# PLD_RTC.net
KiCad netlist of a schematic drawn in Altium Designer
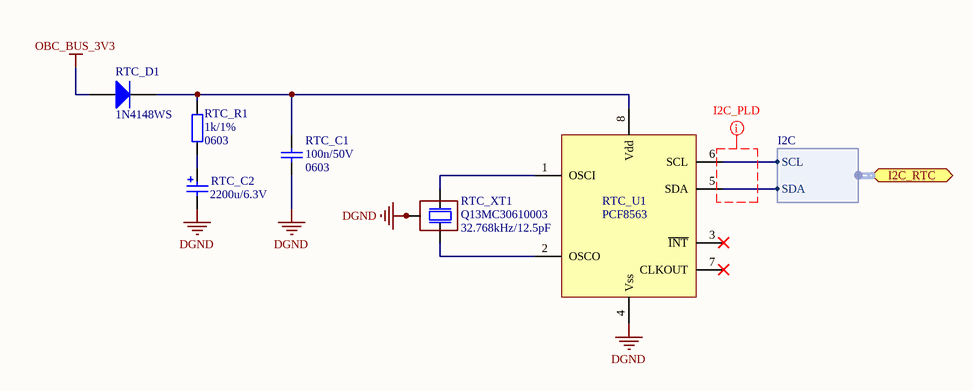
[diagram p0: PLD_RTC.SchDoc]

(export (version "E")
  (design (tool "Eeschema 10.0.6"))
  (components
    (comp (ref "RTC_C1")
      (value "100n/50V")
      (footprint "SMD_Capacitor_0603")
      (description "Ceramic Cap Kemet COTS 100n/50V X7R 0603")
      (fields
        (field (name "MANUFACTURER") "Kemet")
        (field (name "MANUFACTURERPARTNUMBER") "C0603T104K5RALTU")
        (field (name "PACKAGE") "0603")
      )
      (libsource (lib "capacitors") (part "Cer_C0603T104K5RALTU"))
    )
    (comp (ref "RTC_C2")
      (value "2200u/6.3V")
      (footprint "Tant_592D_X")
      (description "Vishay 592D Solid Tantalum Chip Capacitors.")
      (fields
        (field (name "MANUFACTURERPARTNUMBER") "592D228X96R3X2T20H")
        (field (name "MANUFACTURER") "Vishay")
      )
      (libsource (lib "capacitors") (part "Tant_592D228X96R3X2T20H"))
    )
    (comp (ref "RTC_D1")
      (value "1N4148WS")
      (footprint "SOD323")
      (description "Small Signal Fast Switching Diode")
      (fields (field (name "MANUFACTURER") "Vishay"))
      (libsource (lib "diodes") (part "1N4148WS"))
    )
    (comp (ref "RTC_R1")
      (value "1k/1%")
      (footprint "SMD_Resistor_0603")
      (description "1k/1% Vishay CRCW 0603 Resistor. 100mW, 100ppm, 75V.")
      (fields
        (field (name "MANUFACTURER") "Vishay")
        (field (name "MANUFACTURERPARTNUMBER") "CRCW06031K00FKxxxx")
        (field (name "PACKAGE") "0603")
      )
      (libsource (lib "resistors") (part "CRCW06031K00FKxxxx"))
    )
    (comp (ref "RTC_U1")
      (value "~")
      (footprint "TSSOP8_L")
      (description "Real-time clock/calendar")
      (fields (field (name "MANUFACTURER") "NXP") (field (name "MANUFACTURERPARTNUMBER") "PCF8563"))
      (libsource (lib "microcircuits") (part "PCF8563"))
    )
    (comp (ref "RTC_XT1")
      (value "32.768kHz/12.5pF")
      (footprint "Epson_MC-306")
      (description "EPSON MC-306 32.768KHZ 12.5pF Crystal")
      (fields (field (name "MANUFACTURER") "Epson") (field (name "MANUFACTURERPARTNUMBER") "Q13MC30610003"))
      (libsource (lib "crystal") (part "Q13MC30610003"))
    )
  )
  (nets
    (net (code "2") (name "/SCL") (class "Default")
      (node (ref "RTC_U1") (pin "6") (pinfunction "SCL_6") (pintype "passive"))
    )
    (net (code "3") (name "/SDA") (class "Default")
      (node (ref "RTC_U1") (pin "5") (pinfunction "SDA_5") (pintype "passive"))
    )
    (net (code "5") (name "DGND") (class "Default")
      (node (ref "RTC_C1") (pin "2") (pinfunction "2_2") (pintype "passive"))
      (node (ref "RTC_C2") (pin "2") (pinfunction "2_2") (pintype "passive"))
      (node (ref "RTC_U1") (pin "4") (pinfunction "Vss_4") (pintype "passive"))
      (node (ref "RTC_XT1") (pin "2") (pinfunction "NC_2") (pintype "passive"))
      (node (ref "RTC_XT1") (pin "3") (pinfunction "NC_3") (pintype "passive"))
    )
    (net (code "6") (name "Net-(RTC_C2-Pad1)") (class "Default")
      (node (ref "RTC_C2") (pin "1") (pinfunction "1_1") (pintype "passive"))
      (node (ref "RTC_R1") (pin "2") (pinfunction "2_2") (pintype "passive"))
    )
    (net (code "7") (name "Net-(RTC_U1-OSCI)") (class "Default")
      (node (ref "RTC_U1") (pin "1") (pinfunction "OSCI_1") (pintype "passive"))
      (node (ref "RTC_XT1") (pin "1") (pinfunction "inp_1") (pintype "passive"))
    )
    (net (code "8") (name "Net-(RTC_U1-OSCO)") (class "Default")
      (node (ref "RTC_U1") (pin "2") (pinfunction "OSCO_2") (pintype "passive"))
      (node (ref "RTC_XT1") (pin "4") (pinfunction "out_4") (pintype "passive"))
    )
    (net (code "9") (name "Net-(RTC_U1-Vdd)") (class "Default")
      (node (ref "RTC_C1") (pin "1") (pinfunction "1_1") (pintype "passive"))
      (node (ref "RTC_D1") (pin "K") (pinfunction "K_K") (pintype "passive"))
      (node (ref "RTC_R1") (pin "1") (pinfunction "1_1") (pintype "passive"))
      (node (ref "RTC_U1") (pin "8") (pinfunction "Vdd_8") (pintype "passive"))
    )
    (net (code "10") (name "OBC_BUS_3V3") (class "Default")
      (node (ref "RTC_D1") (pin "A") (pinfunction "A_A") (pintype "passive"))
    )
    (net (code "11") (name "unconnected-(RTC_U1-CLKOUT-Pad7)") (class "Default")
      (node (ref "RTC_U1") (pin "7") (pinfunction "CLKOUT_7") (pintype "passive+no_connect"))
    )
    (net (code "12") (name "unconnected-(RTC_U1-~{INT}-Pad3)") (class "Default")
      (node (ref "RTC_U1") (pin "3") (pinfunction "~{INT}_3") (pintype "passive+no_connect"))
    )
  )
)
